# bin_watch.net
KiCad netlist of a schematic drawn in EAGLE
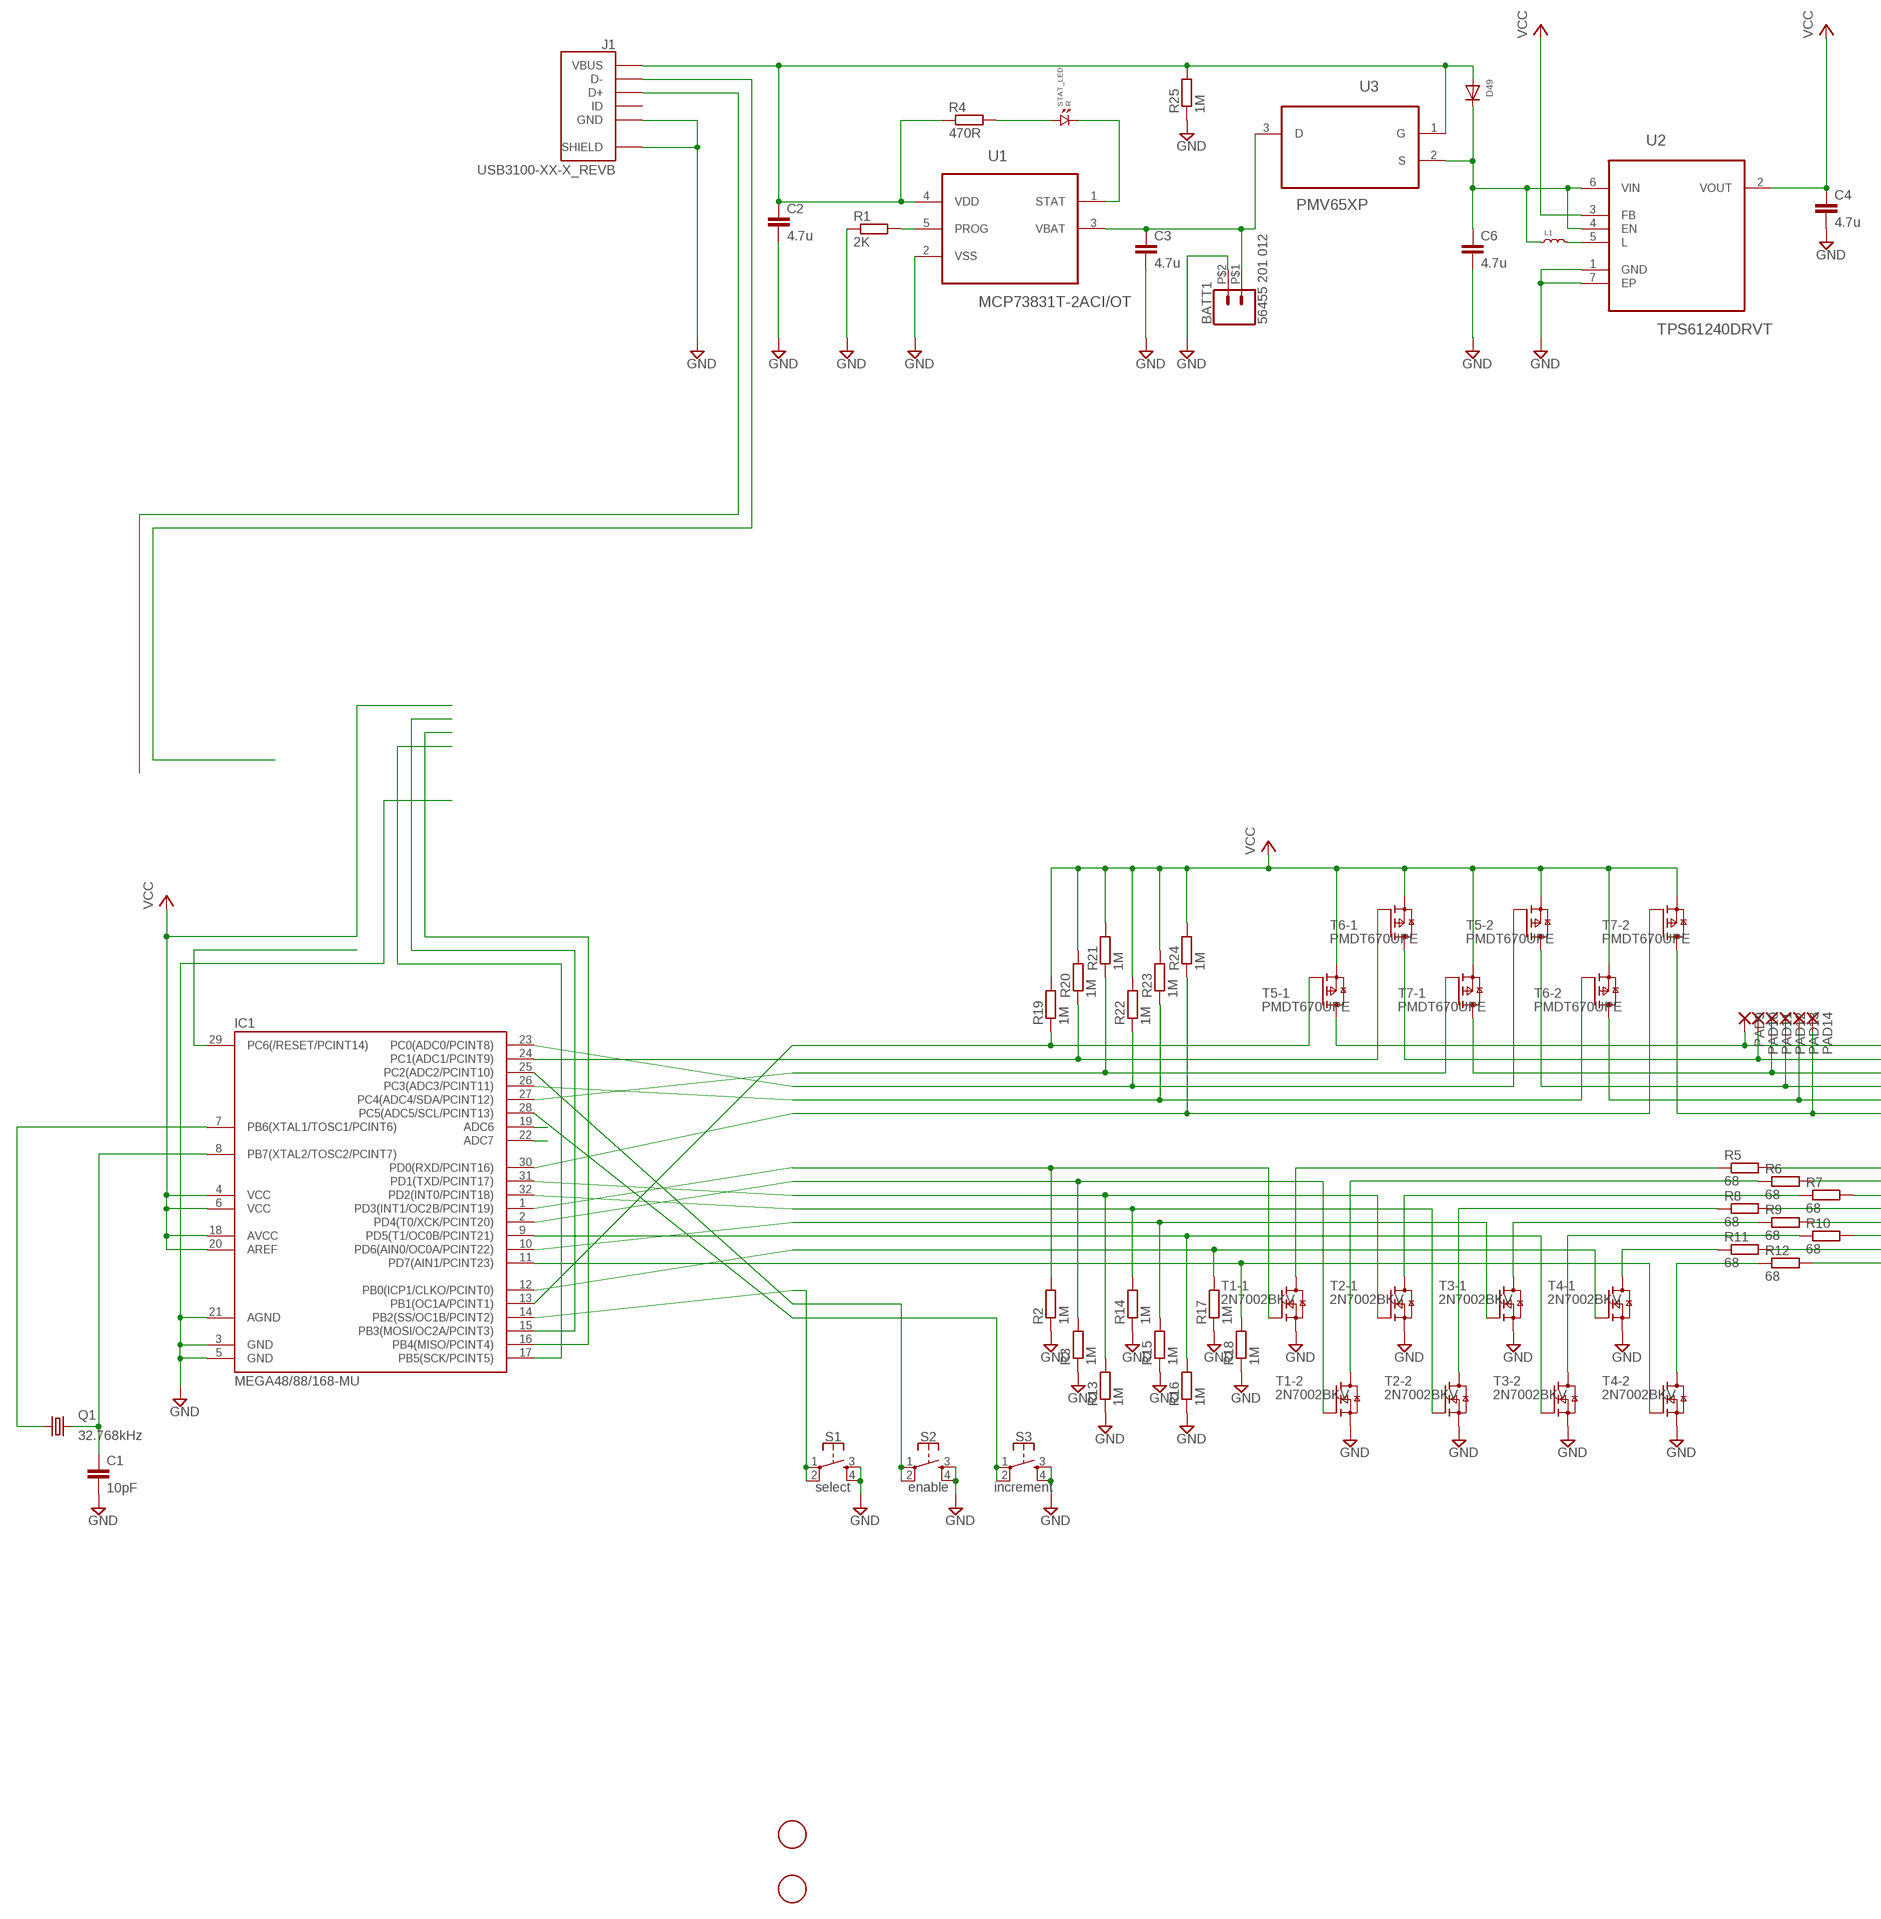
[diagram p0: schematic, sheet 1, part 1 of 2]
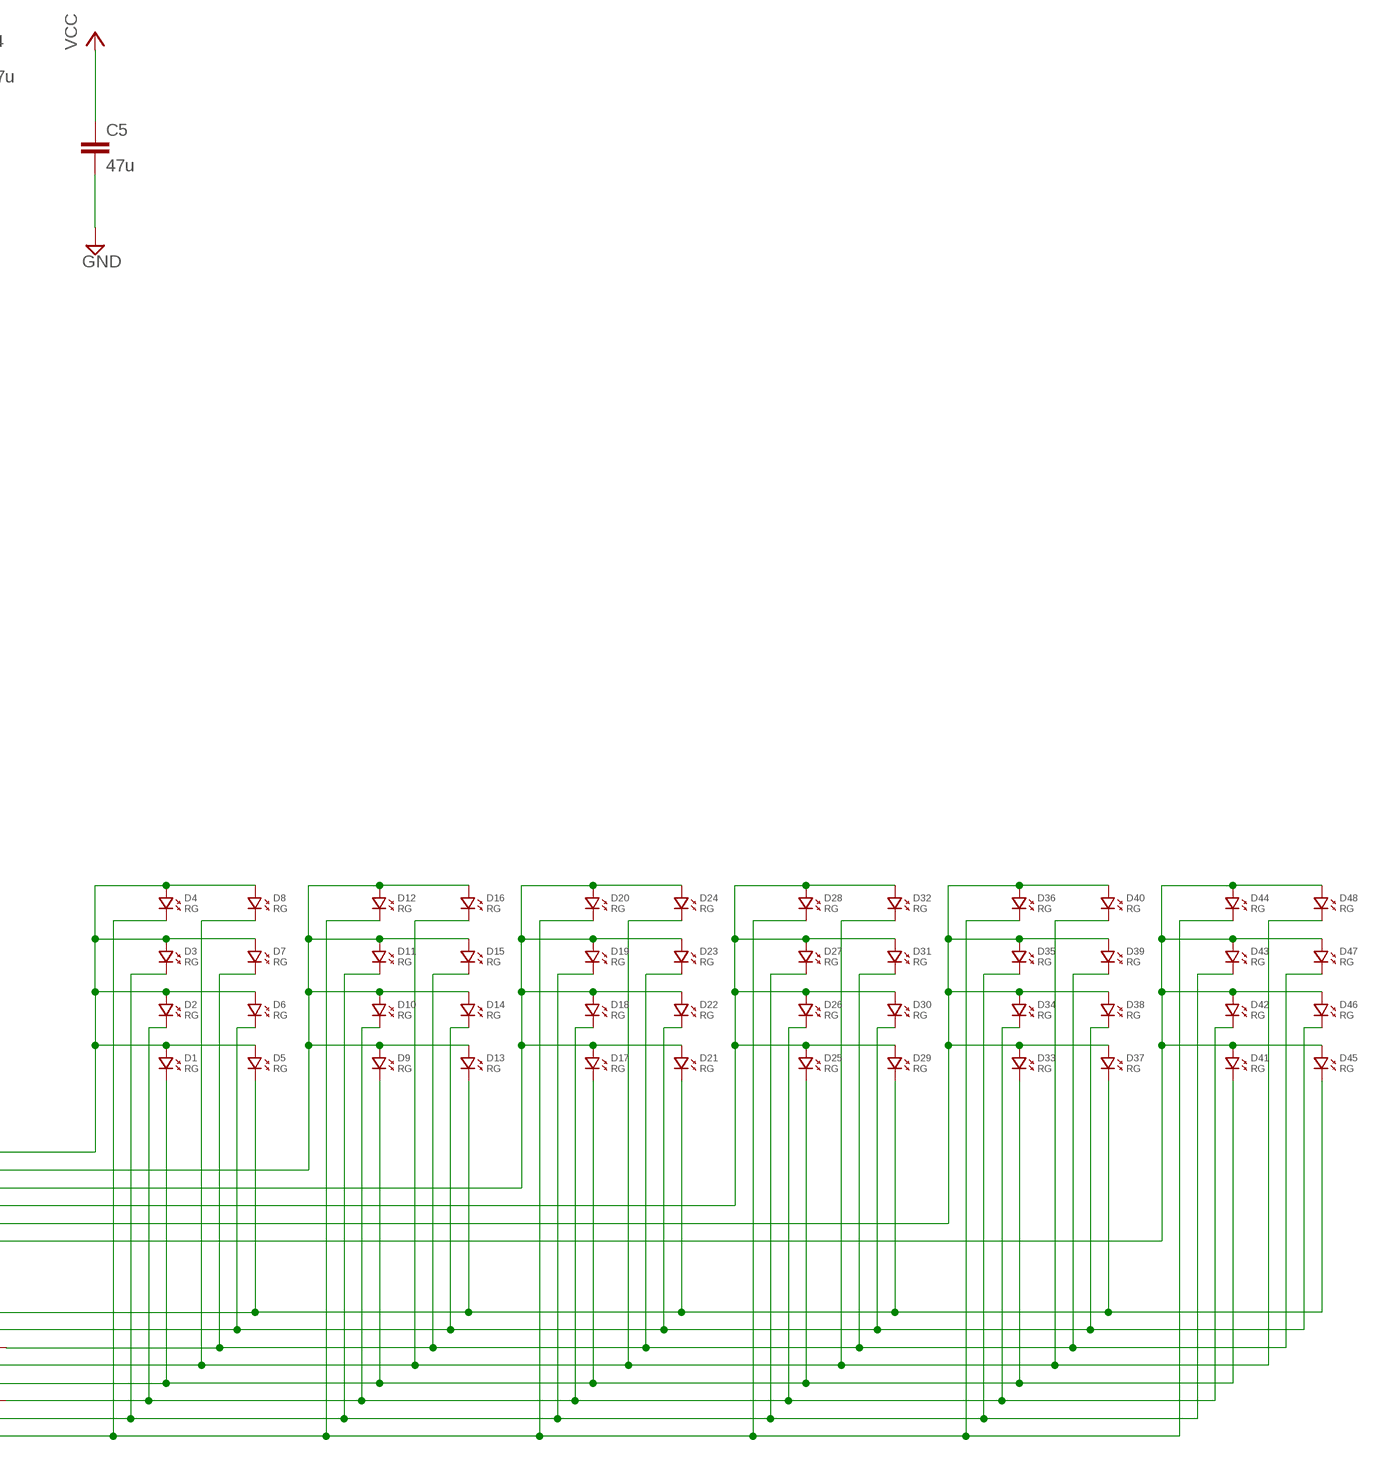
[diagram p1: schematic, sheet 1, part 2 of 2]

(export (version "E")
  (design (tool "Eeschema 10.0.6"))
  (components
    (comp (ref "BATT1")
      (value "56455 201 012")
      (footprint "eagle-import:1X02_BIG")
      (libsource (lib "eagle-import") (part "CONN_02PTH2"))
    )
    (comp (ref "C1")
      (value "10pF")
      (footprint "eagle-import:C0603")
      (libsource (lib "eagle-import") (part "C-EUC0603"))
    )
    (comp (ref "C2")
      (value "4.7u")
      (footprint "eagle-import:C0603")
      (libsource (lib "eagle-import") (part "C-EUC0603"))
    )
    (comp (ref "C3")
      (value "4.7u")
      (footprint "eagle-import:C0603")
      (libsource (lib "eagle-import") (part "C-EUC0603"))
    )
    (comp (ref "C4")
      (value "4.7u")
      (footprint "eagle-import:C0603")
      (libsource (lib "eagle-import") (part "C-EUC0603"))
    )
    (comp (ref "C5")
      (value "47u")
      (footprint "eagle-import:C0603")
      (libsource (lib "eagle-import") (part "C-EUC0603"))
    )
    (comp (ref "C6")
      (value "4.7u")
      (footprint "eagle-import:C0603")
      (libsource (lib "eagle-import") (part "C-EUC0603"))
    )
    (comp (ref "D1")
      (value "RG")
      (footprint "eagle-import:0603.LED")
      (libsource (lib "eagle-import") (part "LED.0603"))
    )
    (comp (ref "D2")
      (value "RG")
      (footprint "eagle-import:0603.LED")
      (libsource (lib "eagle-import") (part "LED.0603"))
    )
    (comp (ref "D3")
      (value "RG")
      (footprint "eagle-import:0603.LED")
      (libsource (lib "eagle-import") (part "LED.0603"))
    )
    (comp (ref "D4")
      (value "RG")
      (footprint "eagle-import:0603.LED")
      (libsource (lib "eagle-import") (part "LED.0603"))
    )
    (comp (ref "D5")
      (value "RG")
      (footprint "eagle-import:0603.LED")
      (libsource (lib "eagle-import") (part "LED.0603"))
    )
    (comp (ref "D6")
      (value "RG")
      (footprint "eagle-import:0603.LED")
      (libsource (lib "eagle-import") (part "LED.0603"))
    )
    (comp (ref "D7")
      (value "RG")
      (footprint "eagle-import:0603.LED")
      (libsource (lib "eagle-import") (part "LED.0603"))
    )
    (comp (ref "D8")
      (value "RG")
      (footprint "eagle-import:0603.LED")
      (libsource (lib "eagle-import") (part "LED.0603"))
    )
    (comp (ref "D9")
      (value "RG")
      (footprint "eagle-import:0603.LED")
      (libsource (lib "eagle-import") (part "LED.0603"))
    )
    (comp (ref "D10")
      (value "RG")
      (footprint "eagle-import:0603.LED")
      (libsource (lib "eagle-import") (part "LED.0603"))
    )
    (comp (ref "D11")
      (value "RG")
      (footprint "eagle-import:0603.LED")
      (libsource (lib "eagle-import") (part "LED.0603"))
    )
    (comp (ref "D12")
      (value "RG")
      (footprint "eagle-import:0603.LED")
      (libsource (lib "eagle-import") (part "LED.0603"))
    )
    (comp (ref "D13")
      (value "RG")
      (footprint "eagle-import:0603.LED")
      (libsource (lib "eagle-import") (part "LED.0603"))
    )
    (comp (ref "D14")
      (value "RG")
      (footprint "eagle-import:0603.LED")
      (libsource (lib "eagle-import") (part "LED.0603"))
    )
    (comp (ref "D15")
      (value "RG")
      (footprint "eagle-import:0603.LED")
      (libsource (lib "eagle-import") (part "LED.0603"))
    )
    (comp (ref "D16")
      (value "RG")
      (footprint "eagle-import:0603.LED")
      (libsource (lib "eagle-import") (part "LED.0603"))
    )
    (comp (ref "D17")
      (value "RG")
      (footprint "eagle-import:0603.LED")
      (libsource (lib "eagle-import") (part "LED.0603"))
    )
    (comp (ref "D18")
      (value "RG")
      (footprint "eagle-import:0603.LED")
      (libsource (lib "eagle-import") (part "LED.0603"))
    )
    (comp (ref "D19")
      (value "RG")
      (footprint "eagle-import:0603.LED")
      (libsource (lib "eagle-import") (part "LED.0603"))
    )
    (comp (ref "D20")
      (value "RG")
      (footprint "eagle-import:0603.LED")
      (libsource (lib "eagle-import") (part "LED.0603"))
    )
    (comp (ref "D21")
      (value "RG")
      (footprint "eagle-import:0603.LED")
      (libsource (lib "eagle-import") (part "LED.0603"))
    )
    (comp (ref "D22")
      (value "RG")
      (footprint "eagle-import:0603.LED")
      (libsource (lib "eagle-import") (part "LED.0603"))
    )
    (comp (ref "D23")
      (value "RG")
      (footprint "eagle-import:0603.LED")
      (libsource (lib "eagle-import") (part "LED.0603"))
    )
    (comp (ref "D24")
      (value "RG")
      (footprint "eagle-import:0603.LED")
      (libsource (lib "eagle-import") (part "LED.0603"))
    )
    (comp (ref "D25")
      (value "RG")
      (footprint "eagle-import:0603.LED")
      (libsource (lib "eagle-import") (part "LED.0603"))
    )
    (comp (ref "D26")
      (value "RG")
      (footprint "eagle-import:0603.LED")
      (libsource (lib "eagle-import") (part "LED.0603"))
    )
    (comp (ref "D27")
      (value "RG")
      (footprint "eagle-import:0603.LED")
      (libsource (lib "eagle-import") (part "LED.0603"))
    )
    (comp (ref "D28")
      (value "RG")
      (footprint "eagle-import:0603.LED")
      (libsource (lib "eagle-import") (part "LED.0603"))
    )
    (comp (ref "D29")
      (value "RG")
      (footprint "eagle-import:0603.LED")
      (libsource (lib "eagle-import") (part "LED.0603"))
    )
    (comp (ref "D30")
      (value "RG")
      (footprint "eagle-import:0603.LED")
      (libsource (lib "eagle-import") (part "LED.0603"))
    )
    (comp (ref "D31")
      (value "RG")
      (footprint "eagle-import:0603.LED")
      (libsource (lib "eagle-import") (part "LED.0603"))
    )
    (comp (ref "D32")
      (value "RG")
      (footprint "eagle-import:0603.LED")
      (libsource (lib "eagle-import") (part "LED.0603"))
    )
    (comp (ref "D33")
      (value "RG")
      (footprint "eagle-import:0603.LED")
      (libsource (lib "eagle-import") (part "LED.0603"))
    )
    (comp (ref "D34")
      (value "RG")
      (footprint "eagle-import:0603.LED")
      (libsource (lib "eagle-import") (part "LED.0603"))
    )
    (comp (ref "D35")
      (value "RG")
      (footprint "eagle-import:0603.LED")
      (libsource (lib "eagle-import") (part "LED.0603"))
    )
    (comp (ref "D36")
      (value "RG")
      (footprint "eagle-import:0603.LED")
      (libsource (lib "eagle-import") (part "LED.0603"))
    )
    (comp (ref "D37")
      (value "RG")
      (footprint "eagle-import:0603.LED")
      (libsource (lib "eagle-import") (part "LED.0603"))
    )
    (comp (ref "D38")
      (value "RG")
      (footprint "eagle-import:0603.LED")
      (libsource (lib "eagle-import") (part "LED.0603"))
    )
    (comp (ref "D39")
      (value "RG")
      (footprint "eagle-import:0603.LED")
      (libsource (lib "eagle-import") (part "LED.0603"))
    )
    (comp (ref "D40")
      (value "RG")
      (footprint "eagle-import:0603.LED")
      (libsource (lib "eagle-import") (part "LED.0603"))
    )
    (comp (ref "D41")
      (value "RG")
      (footprint "eagle-import:0603.LED")
      (libsource (lib "eagle-import") (part "LED.0603"))
    )
    (comp (ref "D42")
      (value "RG")
      (footprint "eagle-import:0603.LED")
      (libsource (lib "eagle-import") (part "LED.0603"))
    )
    (comp (ref "D43")
      (value "RG")
      (footprint "eagle-import:0603.LED")
      (libsource (lib "eagle-import") (part "LED.0603"))
    )
    (comp (ref "D44")
      (value "RG")
      (footprint "eagle-import:0603.LED")
      (libsource (lib "eagle-import") (part "LED.0603"))
    )
    (comp (ref "D45")
      (value "RG")
      (footprint "eagle-import:0603.LED")
      (libsource (lib "eagle-import") (part "LED.0603"))
    )
    (comp (ref "D46")
      (value "RG")
      (footprint "eagle-import:0603.LED")
      (libsource (lib "eagle-import") (part "LED.0603"))
    )
    (comp (ref "D47")
      (value "RG")
      (footprint "eagle-import:0603.LED")
      (libsource (lib "eagle-import") (part "LED.0603"))
    )
    (comp (ref "D48")
      (value "RG")
      (footprint "eagle-import:0603.LED")
      (libsource (lib "eagle-import") (part "LED.0603"))
    )
    (comp (ref "D49")
      (value "DIODESOD-523")
      (footprint "eagle-import:SOD-523")
      (libsource (lib "eagle-import") (part "DIODESOD-523"))
    )
    (comp (ref "IC1")
      (value "MEGA48/88/168-MU")
      (footprint "eagle-import:MLF32")
      (libsource (lib "eagle-import") (part "MEGA48/88/168-MU"))
    )
    (comp (ref "J1")
      (value "USB3100-XX-X_REVB")
      (footprint "eagle-import:GCT_USB3100-XX-X_REVB")
      (fields (field (name "MF") "Global Connector Technology") (field (name "MP") "USB3100-30-A"))
      (libsource (lib "eagle-import") (part "USB3100-XX-X_REVB"))
    )
    (comp (ref "L1")
      (value "RF-INDUCTOR.0805")
      (footprint "eagle-import:0805")
      (libsource (lib "eagle-import") (part "RF-INDUCTOR.0805"))
    )
    (comp (ref "PAD9")
      (value "SMD2")
      (footprint "eagle-import:SMD1,27-2,54")
      (libsource (lib "eagle-import") (part "SMD2"))
    )
    (comp (ref "PAD10")
      (value "SMD2")
      (footprint "eagle-import:SMD1,27-2,54")
      (libsource (lib "eagle-import") (part "SMD2"))
    )
    (comp (ref "PAD11")
      (value "SMD2")
      (footprint "eagle-import:SMD1,27-2,54")
      (libsource (lib "eagle-import") (part "SMD2"))
    )
    (comp (ref "PAD12")
      (value "SMD2")
      (footprint "eagle-import:SMD1,27-2,54")
      (libsource (lib "eagle-import") (part "SMD2"))
    )
    (comp (ref "PAD13")
      (value "SMD2")
      (footprint "eagle-import:SMD1,27-2,54")
      (libsource (lib "eagle-import") (part "SMD2"))
    )
    (comp (ref "PAD14")
      (value "SMD2")
      (footprint "eagle-import:SMD1,27-2,54")
      (libsource (lib "eagle-import") (part "SMD2"))
    )
    (comp (ref "Q1")
      (value "32.768kHz")
      (footprint "eagle-import:3.2X1.5")
      (libsource (lib "eagle-import") (part "KX-327-NHF"))
    )
    (comp (ref "R1")
      (value "2K")
      (footprint "eagle-import:R0603")
      (libsource (lib "eagle-import") (part "R-EU_R0603"))
    )
    (comp (ref "R2")
      (value "1M")
      (footprint "eagle-import:R0603")
      (libsource (lib "eagle-import") (part "R-EU_R0603"))
    )
    (comp (ref "R3")
      (value "1M")
      (footprint "eagle-import:R0603")
      (libsource (lib "eagle-import") (part "R-EU_R0603"))
    )
    (comp (ref "R4")
      (value "470R")
      (footprint "eagle-import:R0603")
      (libsource (lib "eagle-import") (part "R-EU_R0603"))
    )
    (comp (ref "R5")
      (value "68")
      (footprint "eagle-import:R0603")
      (libsource (lib "eagle-import") (part "R-EU_R0603"))
    )
    (comp (ref "R6")
      (value "68")
      (footprint "eagle-import:R0603")
      (libsource (lib "eagle-import") (part "R-EU_R0603"))
    )
    (comp (ref "R7")
      (value "68")
      (footprint "eagle-import:R0603")
      (libsource (lib "eagle-import") (part "R-EU_R0603"))
    )
    (comp (ref "R8")
      (value "68")
      (footprint "eagle-import:R0603")
      (libsource (lib "eagle-import") (part "R-EU_R0603"))
    )
    (comp (ref "R9")
      (value "68")
      (footprint "eagle-import:R0603")
      (libsource (lib "eagle-import") (part "R-EU_R0603"))
    )
    (comp (ref "R10")
      (value "68")
      (footprint "eagle-import:R0603")
      (libsource (lib "eagle-import") (part "R-EU_R0603"))
    )
    (comp (ref "R11")
      (value "68")
      (footprint "eagle-import:R0603")
      (libsource (lib "eagle-import") (part "R-EU_R0603"))
    )
    (comp (ref "R12")
      (value "68")
      (footprint "eagle-import:R0603")
      (libsource (lib "eagle-import") (part "R-EU_R0603"))
    )
    (comp (ref "R13")
      (value "1M")
      (footprint "eagle-import:R0603")
      (libsource (lib "eagle-import") (part "R-EU_R0603"))
    )
    (comp (ref "R14")
      (value "1M")
      (footprint "eagle-import:R0603")
      (libsource (lib "eagle-import") (part "R-EU_R0603"))
    )
    (comp (ref "R15")
      (value "1M")
      (footprint "eagle-import:R0603")
      (libsource (lib "eagle-import") (part "R-EU_R0603"))
    )
    (comp (ref "R16")
      (value "1M")
      (footprint "eagle-import:R0603")
      (libsource (lib "eagle-import") (part "R-EU_R0603"))
    )
    (comp (ref "R17")
      (value "1M")
      (footprint "eagle-import:R0603")
      (libsource (lib "eagle-import") (part "R-EU_R0603"))
    )
    (comp (ref "R18")
      (value "1M")
      (footprint "eagle-import:R0603")
      (libsource (lib "eagle-import") (part "R-EU_R0603"))
    )
    (comp (ref "R19")
      (value "1M")
      (footprint "eagle-import:R0603")
      (libsource (lib "eagle-import") (part "R-EU_R0603"))
    )
    (comp (ref "R20")
      (value "1M")
      (footprint "eagle-import:R0603")
      (libsource (lib "eagle-import") (part "R-EU_R0603"))
    )
    (comp (ref "R21")
      (value "1M")
      (footprint "eagle-import:R0603")
      (libsource (lib "eagle-import") (part "R-EU_R0603"))
    )
    (comp (ref "R22")
      (value "1M")
      (footprint "eagle-import:R0603")
      (libsource (lib "eagle-import") (part "R-EU_R0603"))
    )
    (comp (ref "R23")
      (value "1M")
      (footprint "eagle-import:R0603")
      (libsource (lib "eagle-import") (part "R-EU_R0603"))
    )
    (comp (ref "R24")
      (value "1M")
      (footprint "eagle-import:R0603")
      (libsource (lib "eagle-import") (part "R-EU_R0603"))
    )
    (comp (ref "R25")
      (value "1M")
      (footprint "eagle-import:R0603")
      (libsource (lib "eagle-import") (part "R-EU_R0603"))
    )
    (comp (ref "S1")
      (value "select")
      (footprint "eagle-import:TACTILE_SWITCH_SMD_5.2MM")
      (libsource (lib "eagle-import") (part "MOMENTARY-SWITCH-SPST-2-SMD-5.2MM"))
    )
    (comp (ref "S2")
      (value "enable")
      (footprint "eagle-import:TACTILE_SWITCH_SMD_5.2MM")
      (libsource (lib "eagle-import") (part "MOMENTARY-SWITCH-SPST-2-SMD-5.2MM"))
    )
    (comp (ref "S3")
      (value "increment")
      (footprint "eagle-import:TACTILE_SWITCH_SMD_5.2MM")
      (libsource (lib "eagle-import") (part "MOMENTARY-SWITCH-SPST-2-SMD-5.2MM"))
    )
    (comp (ref "STAT_LED")
      (value "R")
      (footprint "eagle-import:0603.LED")
      (libsource (lib "eagle-import") (part "LED.0603"))
    )
    (comp (ref "T1")
      (value "2N7002BKV")
      (footprint "eagle-import:SOT666")
      (libsource (lib "eagle-import") (part "2N7002BKV"))
    )
    (comp (ref "T2")
      (value "2N7002BKV")
      (footprint "eagle-import:SOT666")
      (libsource (lib "eagle-import") (part "2N7002BKV"))
    )
    (comp (ref "T3")
      (value "2N7002BKV")
      (footprint "eagle-import:SOT666")
      (libsource (lib "eagle-import") (part "2N7002BKV"))
    )
    (comp (ref "T4")
      (value "2N7002BKV")
      (footprint "eagle-import:SOT666")
      (libsource (lib "eagle-import") (part "2N7002BKV"))
    )
    (comp (ref "T5")
      (value "PMDT670UPE")
      (footprint "eagle-import:SOT666")
      (libsource (lib "eagle-import") (part "PMDT670UPE"))
    )
    (comp (ref "T6")
      (value "PMDT670UPE")
      (footprint "eagle-import:SOT666")
      (libsource (lib "eagle-import") (part "PMDT670UPE"))
    )
    (comp (ref "T7")
      (value "PMDT670UPE")
      (footprint "eagle-import:SOT666")
      (libsource (lib "eagle-import") (part "PMDT670UPE"))
    )
    (comp (ref "U$1")
      (value "FIDUCIAL")
      (footprint "eagle-import:FIDUCIAL_1MM")
      (libsource (lib "eagle-import") (part "FIDUCIAL"))
    )
    (comp (ref "U$2")
      (value "FIDUCIAL")
      (footprint "eagle-import:FIDUCIAL_1MM")
      (libsource (lib "eagle-import") (part "FIDUCIAL"))
    )
    (comp (ref "U1")
      (value "MCP73831T-2ACI/OT")
      (footprint "eagle-import:SOT95P280X145-5N")
      (libsource (lib "eagle-import") (part "MCP73831T-2ACI/OT"))
    )
    (comp (ref "U2")
      (value "TPS61240DRVT")
      (footprint "eagle-import:SON65P200X200X80-7N")
      (libsource (lib "eagle-import") (part "TPS61240DRVT"))
    )
    (comp (ref "U3")
      (value "PMV65XP")
      (footprint "eagle-import:SOT95P230X110-3N")
      (fields (field (name "MPN") "PMV48XP"))
      (libsource (lib "eagle-import") (part "PMV48XP"))
    )
  )
  (nets
    (net (code "1") (name "GND") (class "Default")
      (node (ref "BATT1") (pin "P$2") (pinfunction "2_P$2") (pintype "passive"))
      (node (ref "C1") (pin "2") (pinfunction "2_2") (pintype "passive"))
      (node (ref "C2") (pin "2") (pinfunction "2_2") (pintype "passive"))
      (node (ref "C3") (pin "2") (pinfunction "2_2") (pintype "passive"))
      (node (ref "C4") (pin "2") (pinfunction "2_2") (pintype "passive"))
      (node (ref "C5") (pin "2") (pinfunction "2_2") (pintype "passive"))
      (node (ref "C6") (pin "2") (pinfunction "2_2") (pintype "passive"))
      (node (ref "IC1") (pin "21") (pinfunction "AGND_21") (pintype "power_in"))
      (node (ref "IC1") (pin "3") (pinfunction "GND_3") (pintype "power_in"))
      (node (ref "IC1") (pin "5") (pinfunction "GND_5") (pintype "power_in"))
      (node (ref "J1") (pin "5") (pinfunction "GND_5") (pintype "power_in"))
      (node (ref "J1") (pin "6") (pinfunction "SHIELD_6") (pintype "power_in"))
      (node (ref "J1") (pin "7") (pinfunction "SHIELD_7") (pintype "power_in"))
      (node (ref "J1") (pin "8") (pinfunction "SHIELD_8") (pintype "power_in"))
      (node (ref "J1") (pin "9") (pinfunction "SHIELD_9") (pintype "power_in"))
      (node (ref "R1") (pin "1") (pinfunction "1_1") (pintype "passive"))
      (node (ref "R13") (pin "1") (pinfunction "1_1") (pintype "passive"))
      (node (ref "R14") (pin "1") (pinfunction "1_1") (pintype "passive"))
      (node (ref "R15") (pin "1") (pinfunction "1_1") (pintype "passive"))
      (node (ref "R16") (pin "1") (pinfunction "1_1") (pintype "passive"))
      (node (ref "R17") (pin "1") (pinfunction "1_1") (pintype "passive"))
      (node (ref "R18") (pin "1") (pinfunction "1_1") (pintype "passive"))
      (node (ref "R2") (pin "1") (pinfunction "1_1") (pintype "passive"))
      (node (ref "R25") (pin "1") (pinfunction "1_1") (pintype "passive"))
      (node (ref "R3") (pin "1") (pinfunction "1_1") (pintype "passive"))
      (node (ref "S1") (pin "3") (pinfunction "3_3") (pintype "passive"))
      (node (ref "S1") (pin "4") (pinfunction "4_4") (pintype "passive"))
      (node (ref "S2") (pin "3") (pinfunction "3_3") (pintype "passive"))
      (node (ref "S2") (pin "4") (pinfunction "4_4") (pintype "passive"))
      (node (ref "S3") (pin "3") (pinfunction "3_3") (pintype "passive"))
      (node (ref "S3") (pin "4") (pinfunction "4_4") (pintype "passive"))
      (node (ref "T1") (pin "1") (pinfunction "S_1") (pintype "passive"))
      (node (ref "T1") (pin "4") (pinfunction "S_4") (pintype "passive"))
      (node (ref "T2") (pin "1") (pinfunction "S_1") (pintype "passive"))
      (node (ref "T2") (pin "4") (pinfunction "S_4") (pintype "passive"))
      (node (ref "T3") (pin "1") (pinfunction "S_1") (pintype "passive"))
      (node (ref "T3") (pin "4") (pinfunction "S_4") (pintype "passive"))
      (node (ref "T4") (pin "1") (pinfunction "S_1") (pintype "passive"))
      (node (ref "T4") (pin "4") (pinfunction "S_4") (pintype "passive"))
      (node (ref "U1") (pin "2") (pinfunction "VSS_2") (pintype "power_in"))
      (node (ref "U2") (pin "1") (pinfunction "GND_1") (pintype "passive"))
      (node (ref "U2") (pin "7") (pinfunction "EP_7") (pintype "passive"))
    )
    (net (code "2") (name "Net-(BATT1-1)") (class "Default")
      (node (ref "BATT1") (pin "P$1") (pinfunction "1_P$1") (pintype "passive"))
      (node (ref "C3") (pin "1") (pinfunction "1_1") (pintype "passive"))
      (node (ref "U1") (pin "3") (pinfunction "VBAT_3") (pintype "output"))
      (node (ref "U3") (pin "3") (pinfunction "D_3") (pintype "passive"))
    )
    (net (code "3") (name "Net-(D1-1)") (class "Default")
      (node (ref "D1") (pin "P$1") (pinfunction "1_P$1") (pintype "bidirectional"))
      (node (ref "D2") (pin "P$1") (pinfunction "1_P$1") (pintype "bidirectional"))
      (node (ref "D3") (pin "P$1") (pinfunction "1_P$1") (pintype "bidirectional"))
      (node (ref "D4") (pin "P$1") (pinfunction "1_P$1") (pintype "bidirectional"))
      (node (ref "D5") (pin "P$1") (pinfunction "1_P$1") (pintype "bidirectional"))
      (node (ref "D6") (pin "P$1") (pinfunction "1_P$1") (pintype "bidirectional"))
      (node (ref "D7") (pin "P$1") (pinfunction "1_P$1") (pintype "bidirectional"))
      (node (ref "D8") (pin "P$1") (pinfunction "1_P$1") (pintype "bidirectional"))
      (node (ref "PAD9") (pin "1") (pinfunction "P_1") (pintype "passive"))
      (node (ref "T5") (pin "6") (pinfunction "D_6") (pintype "passive"))
    )
    (net (code "4") (name "Net-(D1-2)") (class "Default")
      (node (ref "D1") (pin "P$2") (pinfunction "2_P$2") (pintype "bidirectional"))
      (node (ref "D17") (pin "P$2") (pinfunction "2_P$2") (pintype "bidirectional"))
      (node (ref "D25") (pin "P$2") (pinfunction "2_P$2") (pintype "bidirectional"))
      (node (ref "D33") (pin "P$2") (pinfunction "2_P$2") (pintype "bidirectional"))
      (node (ref "D41") (pin "P$2") (pinfunction "2_P$2") (pintype "bidirectional"))
      (node (ref "D9") (pin "P$2") (pinfunction "2_P$2") (pintype "bidirectional"))
      (node (ref "R9") (pin "2") (pinfunction "2_2") (pintype "passive"))
    )
    (net (code "5") (name "Net-(D10-1)") (class "Default")
      (node (ref "D10") (pin "P$1") (pinfunction "1_P$1") (pintype "bidirectional"))
      (node (ref "D11") (pin "P$1") (pinfunction "1_P$1") (pintype "bidirectional"))
      (node (ref "D12") (pin "P$1") (pinfunction "1_P$1") (pintype "bidirectional"))
      (node (ref "D13") (pin "P$1") (pinfunction "1_P$1") (pintype "bidirectional"))
      (node (ref "D14") (pin "P$1") (pinfunction "1_P$1") (pintype "bidirectional"))
      (node (ref "D15") (pin "P$1") (pinfunction "1_P$1") (pintype "bidirectional"))
      (node (ref "D16") (pin "P$1") (pinfunction "1_P$1") (pintype "bidirectional"))
      (node (ref "D9") (pin "P$1") (pinfunction "1_P$1") (pintype "bidirectional"))
      (node (ref "PAD10") (pin "1") (pinfunction "P_1") (pintype "passive"))
      (node (ref "T6") (pin "6") (pinfunction "D_6") (pintype "passive"))
    )
    (net (code "6") (name "Net-(D10-2)") (class "Default")
      (node (ref "D10") (pin "P$2") (pinfunction "2_P$2") (pintype "bidirectional"))
      (node (ref "D18") (pin "P$2") (pinfunction "2_P$2") (pintype "bidirectional"))
      (node (ref "D2") (pin "P$2") (pinfunction "2_P$2") (pintype "bidirectional"))
      (node (ref "D26") (pin "P$2") (pinfunction "2_P$2") (pintype "bidirectional"))
      (node (ref "D34") (pin "P$2") (pinfunction "2_P$2") (pintype "bidirectional"))
      (node (ref "D42") (pin "P$2") (pinfunction "2_P$2") (pintype "bidirectional"))
      (node (ref "R10") (pin "2") (pinfunction "2_2") (pintype "passive"))
    )
    (net (code "7") (name "Net-(D11-2)") (class "Default")
      (node (ref "D11") (pin "P$2") (pinfunction "2_P$2") (pintype "bidirectional"))
      (node (ref "D19") (pin "P$2") (pinfunction "2_P$2") (pintype "bidirectional"))
      (node (ref "D27") (pin "P$2") (pinfunction "2_P$2") (pintype "bidirectional"))
      (node (ref "D3") (pin "P$2") (pinfunction "2_P$2") (pintype "bidirectional"))
      (node (ref "D35") (pin "P$2") (pinfunction "2_P$2") (pintype "bidirectional"))
      (node (ref "D43") (pin "P$2") (pinfunction "2_P$2") (pintype "bidirectional"))
      (node (ref "R11") (pin "2") (pinfunction "2_2") (pintype "passive"))
    )
    (net (code "8") (name "Net-(D12-2)") (class "Default")
      (node (ref "D12") (pin "P$2") (pinfunction "2_P$2") (pintype "bidirectional"))
      (node (ref "D20") (pin "P$2") (pinfunction "2_P$2") (pintype "bidirectional"))
      (node (ref "D28") (pin "P$2") (pinfunction "2_P$2") (pintype "bidirectional"))
      (node (ref "D36") (pin "P$2") (pinfunction "2_P$2") (pintype "bidirectional"))
      (node (ref "D4") (pin "P$2") (pinfunction "2_P$2") (pintype "bidirectional"))
      (node (ref "D44") (pin "P$2") (pinfunction "2_P$2") (pintype "bidirectional"))
      (node (ref "R12") (pin "2") (pinfunction "2_2") (pintype "passive"))
    )
    (net (code "9") (name "Net-(D13-2)") (class "Default")
      (node (ref "D13") (pin "P$2") (pinfunction "2_P$2") (pintype "bidirectional"))
      (node (ref "D21") (pin "P$2") (pinfunction "2_P$2") (pintype "bidirectional"))
      (node (ref "D29") (pin "P$2") (pinfunction "2_P$2") (pintype "bidirectional"))
      (node (ref "D37") (pin "P$2") (pinfunction "2_P$2") (pintype "bidirectional"))
      (node (ref "D45") (pin "P$2") (pinfunction "2_P$2") (pintype "bidirectional"))
      (node (ref "D5") (pin "P$2") (pinfunction "2_P$2") (pintype "bidirectional"))
      (node (ref "R5") (pin "2") (pinfunction "2_2") (pintype "passive"))
    )
    (net (code "10") (name "Net-(D14-2)") (class "Default")
      (node (ref "D14") (pin "P$2") (pinfunction "2_P$2") (pintype "bidirectional"))
      (node (ref "D22") (pin "P$2") (pinfunction "2_P$2") (pintype "bidirectional"))
      (node (ref "D30") (pin "P$2") (pinfunction "2_P$2") (pintype "bidirectional"))
      (node (ref "D38") (pin "P$2") (pinfunction "2_P$2") (pintype "bidirectional"))
      (node (ref "D46") (pin "P$2") (pinfunction "2_P$2") (pintype "bidirectional"))
      (node (ref "D6") (pin "P$2") (pinfunction "2_P$2") (pintype "bidirectional"))
      (node (ref "R6") (pin "2") (pinfunction "2_2") (pintype "passive"))
    )
    (net (code "11") (name "Net-(D15-2)") (class "Default")
      (node (ref "D15") (pin "P$2") (pinfunction "2_P$2") (pintype "bidirectional"))
      (node (ref "D23") (pin "P$2") (pinfunction "2_P$2") (pintype "bidirectional"))
      (node (ref "D31") (pin "P$2") (pinfunction "2_P$2") (pintype "bidirectional"))
      (node (ref "D39") (pin "P$2") (pinfunction "2_P$2") (pintype "bidirectional"))
      (node (ref "D47") (pin "P$2") (pinfunction "2_P$2") (pintype "bidirectional"))
      (node (ref "D7") (pin "P$2") (pinfunction "2_P$2") (pintype "bidirectional"))
      (node (ref "R7") (pin "2") (pinfunction "2_2") (pintype "passive"))
    )
    (net (code "12") (name "Net-(D16-2)") (class "Default")
      (node (ref "D16") (pin "P$2") (pinfunction "2_P$2") (pintype "bidirectional"))
      (node (ref "D24") (pin "P$2") (pinfunction "2_P$2") (pintype "bidirectional"))
      (node (ref "D32") (pin "P$2") (pinfunction "2_P$2") (pintype "bidirectional"))
      (node (ref "D40") (pin "P$2") (pinfunction "2_P$2") (pintype "bidirectional"))
      (node (ref "D48") (pin "P$2") (pinfunction "2_P$2") (pintype "bidirectional"))
      (node (ref "D8") (pin "P$2") (pinfunction "2_P$2") (pintype "bidirectional"))
      (node (ref "R8") (pin "2") (pinfunction "2_2") (pintype "passive"))
    )
    (net (code "13") (name "Net-(D17-1)") (class "Default")
      (node (ref "D17") (pin "P$1") (pinfunction "1_P$1") (pintype "bidirectional"))
      (node (ref "D18") (pin "P$1") (pinfunction "1_P$1") (pintype "bidirectional"))
      (node (ref "D19") (pin "P$1") (pinfunction "1_P$1") (pintype "bidirectional"))
      (node (ref "D20") (pin "P$1") (pinfunction "1_P$1") (pintype "bidirectional"))
      (node (ref "D21") (pin "P$1") (pinfunction "1_P$1") (pintype "bidirectional"))
      (node (ref "D22") (pin "P$1") (pinfunction "1_P$1") (pintype "bidirectional"))
      (node (ref "D23") (pin "P$1") (pinfunction "1_P$1") (pintype "bidirectional"))
      (node (ref "D24") (pin "P$1") (pinfunction "1_P$1") (pintype "bidirectional"))
      (node (ref "PAD11") (pin "1") (pinfunction "P_1") (pintype "passive"))
      (node (ref "T7") (pin "6") (pinfunction "D_6") (pintype "passive"))
    )
    (net (code "14") (name "Net-(D25-1)") (class "Default")
      (node (ref "D25") (pin "P$1") (pinfunction "1_P$1") (pintype "bidirectional"))
      (node (ref "D26") (pin "P$1") (pinfunction "1_P$1") (pintype "bidirectional"))
      (node (ref "D27") (pin "P$1") (pinfunction "1_P$1") (pintype "bidirectional"))
      (node (ref "D28") (pin "P$1") (pinfunction "1_P$1") (pintype "bidirectional"))
      (node (ref "D29") (pin "P$1") (pinfunction "1_P$1") (pintype "bidirectional"))
      (node (ref "D30") (pin "P$1") (pinfunction "1_P$1") (pintype "bidirectional"))
      (node (ref "D31") (pin "P$1") (pinfunction "1_P$1") (pintype "bidirectional"))
      (node (ref "D32") (pin "P$1") (pinfunction "1_P$1") (pintype "bidirectional"))
      (node (ref "PAD12") (pin "1") (pinfunction "P_1") (pintype "passive"))
      (node (ref "T5") (pin "3") (pinfunction "D_3") (pintype "passive"))
    )
    (net (code "15") (name "Net-(D33-1)") (class "Default")
      (node (ref "D33") (pin "P$1") (pinfunction "1_P$1") (pintype "bidirectional"))
      (node (ref "D34") (pin "P$1") (pinfunction "1_P$1") (pintype "bidirectional"))
      (node (ref "D35") (pin "P$1") (pinfunction "1_P$1") (pintype "bidirectional"))
      (node (ref "D36") (pin "P$1") (pinfunction "1_P$1") (pintype "bidirectional"))
      (node (ref "D37") (pin "P$1") (pinfunction "1_P$1") (pintype "bidirectional"))
      (node (ref "D38") (pin "P$1") (pinfunction "1_P$1") (pintype "bidirectional"))
      (node (ref "D39") (pin "P$1") (pinfunction "1_P$1") (pintype "bidirectional"))
      (node (ref "D40") (pin "P$1") (pinfunction "1_P$1") (pintype "bidirectional"))
      (node (ref "PAD13") (pin "1") (pinfunction "P_1") (pintype "passive"))
      (node (ref "T6") (pin "3") (pinfunction "D_3") (pintype "passive"))
    )
    (net (code "16") (name "Net-(D41-1)") (class "Default")
      (node (ref "D41") (pin "P$1") (pinfunction "1_P$1") (pintype "bidirectional"))
      (node (ref "D42") (pin "P$1") (pinfunction "1_P$1") (pintype "bidirectional"))
      (node (ref "D43") (pin "P$1") (pinfunction "1_P$1") (pintype "bidirectional"))
      (node (ref "D44") (pin "P$1") (pinfunction "1_P$1") (pintype "bidirectional"))
      (node (ref "D45") (pin "P$1") (pinfunction "1_P$1") (pintype "bidirectional"))
      (node (ref "D46") (pin "P$1") (pinfunction "1_P$1") (pintype "bidirectional"))
      (node (ref "D47") (pin "P$1") (pinfunction "1_P$1") (pintype "bidirectional"))
      (node (ref "D48") (pin "P$1") (pinfunction "1_P$1") (pintype "bidirectional"))
      (node (ref "PAD14") (pin "1") (pinfunction "P_1") (pintype "passive"))
      (node (ref "T7") (pin "3") (pinfunction "D_3") (pintype "passive"))
    )
    (net (code "17") (name "Net-(D49-C)") (class "Default")
      (node (ref "C6") (pin "1") (pinfunction "1_1") (pintype "passive"))
      (node (ref "D49") (pin "K") (pinfunction "C_K") (pintype "passive"))
      (node (ref "L1") (pin "1") (pinfunction "1_1") (pintype "passive"))
      (node (ref "U2") (pin "4") (pinfunction "EN_4") (pintype "input"))
      (node (ref "U2") (pin "6") (pinfunction "VIN_6") (pintype "power_in"))
      (node (ref "U3") (pin "2") (pinfunction "S_2") (pintype "passive"))
    )
    (net (code "18") (name "Net-(IC1-PB0(ICP1{slash}CLKO{slash}PCINT0))") (class "Default")
      (node (ref "IC1") (pin "12") (pinfunction "PB0(ICP1/CLKO/PCINT0)_12") (pintype "bidirectional"))
      (node (ref "R17") (pin "2") (pinfunction "2_2") (pintype "passive"))
      (node (ref "T4") (pin "2") (pinfunction "G_2") (pintype "passive"))
    )
    (net (code "19") (name "Net-(IC1-PB1(OC1A{slash}PCINT1))") (class "Default")
      (node (ref "IC1") (pin "13") (pinfunction "PB1(OC1A/PCINT1)_13") (pintype "bidirectional"))
      (node (ref "R19") (pin "1") (pinfunction "1_1") (pintype "passive"))
      (node (ref "T5") (pin "2") (pinfunction "G_2") (pintype "passive"))
    )
    (net (code "20") (name "Net-(IC1-PB2(SS{slash}OC1B{slash}PCINT2))") (class "Default")
      (node (ref "IC1") (pin "14") (pinfunction "PB2(SS/OC1B/PCINT2)_14") (pintype "bidirectional"))
      (node (ref "S1") (pin "1") (pinfunction "1_1") (pintype "passive"))
      (node (ref "S1") (pin "2") (pinfunction "2_2") (pintype "passive"))
    )
    (net (code "21") (name "Net-(IC1-PB6(XTAL1{slash}TOSC1{slash}PCINT6))") (class "Default")
      (node (ref "IC1") (pin "7") (pinfunction "PB6(XTAL1/TOSC1/PCINT6)_7") (pintype "bidirectional"))
      (node (ref "Q1") (pin "1") (pinfunction "1_1") (pintype "passive"))
    )
    (net (code "22") (name "Net-(IC1-PB7(XTAL2{slash}TOSC2{slash}PCINT7))") (class "Default")
      (node (ref "C1") (pin "1") (pinfunction "1_1") (pintype "passive"))
      (node (ref "IC1") (pin "8") (pinfunction "PB7(XTAL2/TOSC2/PCINT7)_8") (pintype "bidirectional"))
      (node (ref "Q1") (pin "2") (pinfunction "2_2") (pintype "passive"))
    )
    (net (code "23") (name "Net-(IC1-PC0(ADC0{slash}PCINT8))") (class "Default")
      (node (ref "IC1") (pin "23") (pinfunction "PC0(ADC0/PCINT8)_23") (pintype "bidirectional"))
      (node (ref "R22") (pin "1") (pinfunction "1_1") (pintype "passive"))
      (node (ref "T5") (pin "5") (pinfunction "G_5") (pintype "passive"))
    )
    (net (code "24") (name "Net-(IC1-PC1(ADC1{slash}PCINT9))") (class "Default")
      (node (ref "IC1") (pin "24") (pinfunction "PC1(ADC1/PCINT9)_24") (pintype "bidirectional"))
      (node (ref "R20") (pin "1") (pinfunction "1_1") (pintype "passive"))
      (node (ref "T6") (pin "2") (pinfunction "G_2") (pintype "passive"))
    )
    (net (code "25") (name "Net-(IC1-PC2(ADC2{slash}PCINT10))") (class "Default")
      (node (ref "IC1") (pin "25") (pinfunction "PC2(ADC2/PCINT10)_25") (pintype "bidirectional"))
      (node (ref "S2") (pin "1") (pinfunction "1_1") (pintype "passive"))
      (node (ref "S2") (pin "2") (pinfunction "2_2") (pintype "passive"))
    )
    (net (code "26") (name "Net-(IC1-PC3(ADC3{slash}PCINT11))") (class "Default")
      (node (ref "IC1") (pin "26") (pinfunction "PC3(ADC3/PCINT11)_26") (pintype "bidirectional"))
      (node (ref "R23") (pin "1") (pinfunction "1_1") (pintype "passive"))
      (node (ref "T6") (pin "5") (pinfunction "G_5") (pintype "passive"))
    )
    (net (code "27") (name "Net-(IC1-PC4(ADC4{slash}SDA{slash}PCINT12))") (class "Default")
      (node (ref "IC1") (pin "27") (pinfunction "PC4(ADC4/SDA/PCINT12)_27") (pintype "bidirectional"))
      (node (ref "R21") (pin "1") (pinfunction "1_1") (pintype "passive"))
      (node (ref "T7") (pin "2") (pinfunction "G_2") (pintype "passive"))
    )
    (net (code "28") (name "Net-(IC1-PC5(ADC5{slash}SCL{slash}PCINT13))") (class "Default")
      (node (ref "IC1") (pin "28") (pinfunction "PC5(ADC5/SCL/PCINT13)_28") (pintype "bidirectional"))
      (node (ref "S3") (pin "1") (pinfunction "1_1") (pintype "passive"))
      (node (ref "S3") (pin "2") (pinfunction "2_2") (pintype "passive"))
    )
    (net (code "29") (name "Net-(IC1-PD0(RXD{slash}PCINT16))") (class "Default")
      (node (ref "IC1") (pin "30") (pinfunction "PD0(RXD/PCINT16)_30") (pintype "bidirectional"))
      (node (ref "R24") (pin "1") (pinfunction "1_1") (pintype "passive"))
      (node (ref "T7") (pin "5") (pinfunction "G_5") (pintype "passive"))
    )
    (net (code "30") (name "Net-(IC1-PD1(TXD{slash}PCINT17))") (class "Default")
      (node (ref "IC1") (pin "31") (pinfunction "PD1(TXD/PCINT17)_31") (pintype "bidirectional"))
      (node (ref "R13") (pin "2") (pinfunction "2_2") (pintype "passive"))
      (node (ref "T2") (pin "2") (pinfunction "G_2") (pintype "passive"))
    )
    (net (code "31") (name "Net-(IC1-PD2(INT0{slash}PCINT18))") (class "Default")
      (node (ref "IC1") (pin "32") (pinfunction "PD2(INT0/PCINT18)_32") (pintype "bidirectional"))
      (node (ref "R14") (pin "2") (pinfunction "2_2") (pintype "passive"))
      (node (ref "T2") (pin "5") (pinfunction "G_5") (pintype "passive"))
    )
    (net (code "32") (name "Net-(IC1-PD3(INT1{slash}OC2B{slash}PCINT19))") (class "Default")
      (node (ref "IC1") (pin "1") (pinfunction "PD3(INT1/OC2B/PCINT19)_1") (pintype "bidirectional"))
      (node (ref "R2") (pin "2") (pinfunction "2_2") (pintype "passive"))
      (node (ref "T1") (pin "2") (pinfunction "G_2") (pintype "passive"))
    )
    (net (code "33") (name "Net-(IC1-PD4(T0{slash}XCK{slash}PCINT20))") (class "Default")
      (node (ref "IC1") (pin "2") (pinfunction "PD4(T0/XCK/PCINT20)_2") (pintype "bidirectional"))
      (node (ref "R3") (pin "2") (pinfunction "2_2") (pintype "passive"))
      (node (ref "T1") (pin "5") (pinfunction "G_5") (pintype "passive"))
    )
    (net (code "34") (name "Net-(IC1-PD5(T1{slash}OC0B{slash}PCINT21))") (class "Default")
      (node (ref "IC1") (pin "9") (pinfunction "PD5(T1/OC0B/PCINT21)_9") (pintype "bidirectional"))
      (node (ref "R16") (pin "2") (pinfunction "2_2") (pintype "passive"))
      (node (ref "T3") (pin "5") (pinfunction "G_5") (pintype "passive"))
    )
    (net (code "35") (name "Net-(IC1-PD6(AIN0{slash}OC0A{slash}PCINT22))") (class "Default")
      (node (ref "IC1") (pin "10") (pinfunction "PD6(AIN0/OC0A/PCINT22)_10") (pintype "bidirectional"))
      (node (ref "R15") (pin "2") (pinfunction "2_2") (pintype "passive"))
      (node (ref "T3") (pin "2") (pinfunction "G_2") (pintype "passive"))
    )
    (net (code "36") (name "Net-(IC1-PD7(AIN1{slash}PCINT23))") (class "Default")
      (node (ref "IC1") (pin "11") (pinfunction "PD7(AIN1/PCINT23)_11") (pintype "bidirectional"))
      (node (ref "R18") (pin "2") (pinfunction "2_2") (pintype "passive"))
      (node (ref "T4") (pin "5") (pinfunction "G_5") (pintype "passive"))
    )
    (net (code "37") (name "Net-(J1-VBUS)") (class "Default")
      (node (ref "C2") (pin "1") (pinfunction "1_1") (pintype "passive"))
      (node (ref "D49") (pin "A") (pinfunction "A_A") (pintype "passive"))
      (node (ref "J1") (pin "1") (pinfunction "VBUS_1") (pintype "power_in"))
      (node (ref "R25") (pin "2") (pinfunction "2_2") (pintype "passive"))
      (node (ref "R4") (pin "1") (pinfunction "1_1") (pintype "passive"))
      (node (ref "U1") (pin "4") (pinfunction "VDD_4") (pintype "power_in"))
      (node (ref "U3") (pin "1") (pinfunction "G_1") (pintype "passive"))
    )
    (net (code "38") (name "Net-(STAT_LED-1)") (class "Default")
      (node (ref "R4") (pin "2") (pinfunction "2_2") (pintype "passive"))
      (node (ref "STAT_LED") (pin "P$1") (pinfunction "1_P$1") (pintype "bidirectional"))
    )
    (net (code "39") (name "Net-(STAT_LED-2)") (class "Default")
      (node (ref "STAT_LED") (pin "P$2") (pinfunction "2_P$2") (pintype "bidirectional"))
      (node (ref "U1") (pin "1") (pinfunction "STAT_1") (pintype "output"))
    )
    (net (code "40") (name "Net-(T1A-D)") (class "Default")
      (node (ref "R5") (pin "1") (pinfunction "1_1") (pintype "passive"))
      (node (ref "T1") (pin "6") (pinfunction "D_6") (pintype "passive"))
    )
    (net (code "41") (name "Net-(T1B-D)") (class "Default")
      (node (ref "R6") (pin "1") (pinfunction "1_1") (pintype "passive"))
      (node (ref "T1") (pin "3") (pinfunction "D_3") (pintype "passive"))
    )
    (net (code "42") (name "Net-(T2A-D)") (class "Default")
      (node (ref "R7") (pin "1") (pinfunction "1_1") (pintype "passive"))
      (node (ref "T2") (pin "6") (pinfunction "D_6") (pintype "passive"))
    )
    (net (code "43") (name "Net-(T2B-D)") (class "Default")
      (node (ref "R8") (pin "1") (pinfunction "1_1") (pintype "passive"))
      (node (ref "T2") (pin "3") (pinfunction "D_3") (pintype "passive"))
    )
    (net (code "44") (name "Net-(T3A-D)") (class "Default")
      (node (ref "R9") (pin "1") (pinfunction "1_1") (pintype "passive"))
      (node (ref "T3") (pin "6") (pinfunction "D_6") (pintype "passive"))
    )
    (net (code "45") (name "Net-(T3B-D)") (class "Default")
      (node (ref "R10") (pin "1") (pinfunction "1_1") (pintype "passive"))
      (node (ref "T3") (pin "3") (pinfunction "D_3") (pintype "passive"))
    )
    (net (code "46") (name "Net-(T4A-D)") (class "Default")
      (node (ref "R11") (pin "1") (pinfunction "1_1") (pintype "passive"))
      (node (ref "T4") (pin "6") (pinfunction "D_6") (pintype "passive"))
    )
    (net (code "47") (name "Net-(T4B-D)") (class "Default")
      (node (ref "R12") (pin "1") (pinfunction "1_1") (pintype "passive"))
      (node (ref "T4") (pin "3") (pinfunction "D_3") (pintype "passive"))
    )
    (net (code "48") (name "Net-(U1-PROG)") (class "Default")
      (node (ref "R1") (pin "2") (pinfunction "2_2") (pintype "passive"))
      (node (ref "U1") (pin "5") (pinfunction "PROG_5") (pintype "input"))
    )
    (net (code "49") (name "Net-(U2-L)") (class "Default")
      (node (ref "L1") (pin "2") (pinfunction "2_2") (pintype "passive"))
      (node (ref "U2") (pin "5") (pinfunction "L_5") (pintype "input"))
    )
    (net (code "50") (name "VCC") (class "Default")
      (node (ref "C4") (pin "1") (pinfunction "1_1") (pintype "passive"))
      (node (ref "C5") (pin "1") (pinfunction "1_1") (pintype "passive"))
      (node (ref "IC1") (pin "18") (pinfunction "AVCC_18") (pintype "passive"))
      (node (ref "IC1") (pin "20") (pinfunction "AREF_20") (pintype "passive"))
      (node (ref "IC1") (pin "4") (pinfunction "VCC_4") (pintype "power_in"))
      (node (ref "IC1") (pin "6") (pinfunction "VCC_6") (pintype "power_in"))
      (node (ref "R19") (pin "2") (pinfunction "2_2") (pintype "passive"))
      (node (ref "R20") (pin "2") (pinfunction "2_2") (pintype "passive"))
      (node (ref "R21") (pin "2") (pinfunction "2_2") (pintype "passive"))
      (node (ref "R22") (pin "2") (pinfunction "2_2") (pintype "passive"))
      (node (ref "R23") (pin "2") (pinfunction "2_2") (pintype "passive"))
      (node (ref "R24") (pin "2") (pinfunction "2_2") (pintype "passive"))
      (node (ref "T5") (pin "1") (pinfunction "S_1") (pintype "passive"))
      (node (ref "T5") (pin "4") (pinfunction "S_4") (pintype "passive"))
      (node (ref "T6") (pin "1") (pinfunction "S_1") (pintype "passive"))
      (node (ref "T6") (pin "4") (pinfunction "S_4") (pintype "passive"))
      (node (ref "T7") (pin "1") (pinfunction "S_1") (pintype "passive"))
      (node (ref "T7") (pin "4") (pinfunction "S_4") (pintype "passive"))
      (node (ref "U2") (pin "2") (pinfunction "VOUT_2") (pintype "output"))
      (node (ref "U2") (pin "3") (pinfunction "FB_3") (pintype "input"))
    )
    (net (code "51") (name "unconnected-(IC1-ADC6-Pad19)") (class "Default")
      (node (ref "IC1") (pin "19") (pinfunction "ADC6_19") (pintype "passive"))
    )
    (net (code "52") (name "unconnected-(IC1-ADC7-Pad22)") (class "Default")
      (node (ref "IC1") (pin "22") (pinfunction "ADC7_22") (pintype "passive"))
    )
    (net (code "53") (name "unconnected-(IC1-PB3(MOSI{slash}OC2A{slash}PCINT3)-Pad15)") (class "Default")
      (node (ref "IC1") (pin "15") (pinfunction "PB3(MOSI/OC2A/PCINT3)_15") (pintype "bidirectional"))
    )
    (net (code "54") (name "unconnected-(IC1-PB4(MISO{slash}PCINT4)-Pad16)") (class "Default")
      (node (ref "IC1") (pin "16") (pinfunction "PB4(MISO/PCINT4)_16") (pintype "bidirectional"))
    )
    (net (code "55") (name "unconnected-(IC1-PB5(SCK{slash}PCINT5)-Pad17)") (class "Default")
      (node (ref "IC1") (pin "17") (pinfunction "PB5(SCK/PCINT5)_17") (pintype "bidirectional"))
    )
    (net (code "56") (name "unconnected-(IC1-PC6({slash}RESET{slash}PCINT14)-Pad29)") (class "Default")
      (node (ref "IC1") (pin "29") (pinfunction "PC6(/RESET/PCINT14)_29") (pintype "bidirectional"))
    )
    (net (code "57") (name "unconnected-(J1-D+-Pad3)") (class "Default")
      (node (ref "J1") (pin "3") (pinfunction "D+_3") (pintype "bidirectional"))
    )
    (net (code "58") (name "unconnected-(J1-D--Pad2)") (class "Default")
      (node (ref "J1") (pin "2") (pinfunction "D-_2") (pintype "bidirectional"))
    )
    (net (code "59") (name "unconnected-(J1-ID-Pad4)") (class "Default")
      (node (ref "J1") (pin "4") (pinfunction "ID_4") (pintype "bidirectional"))
    )
  )
)
